# main.net
KiCad netlist of a schematic drawn in EAGLE
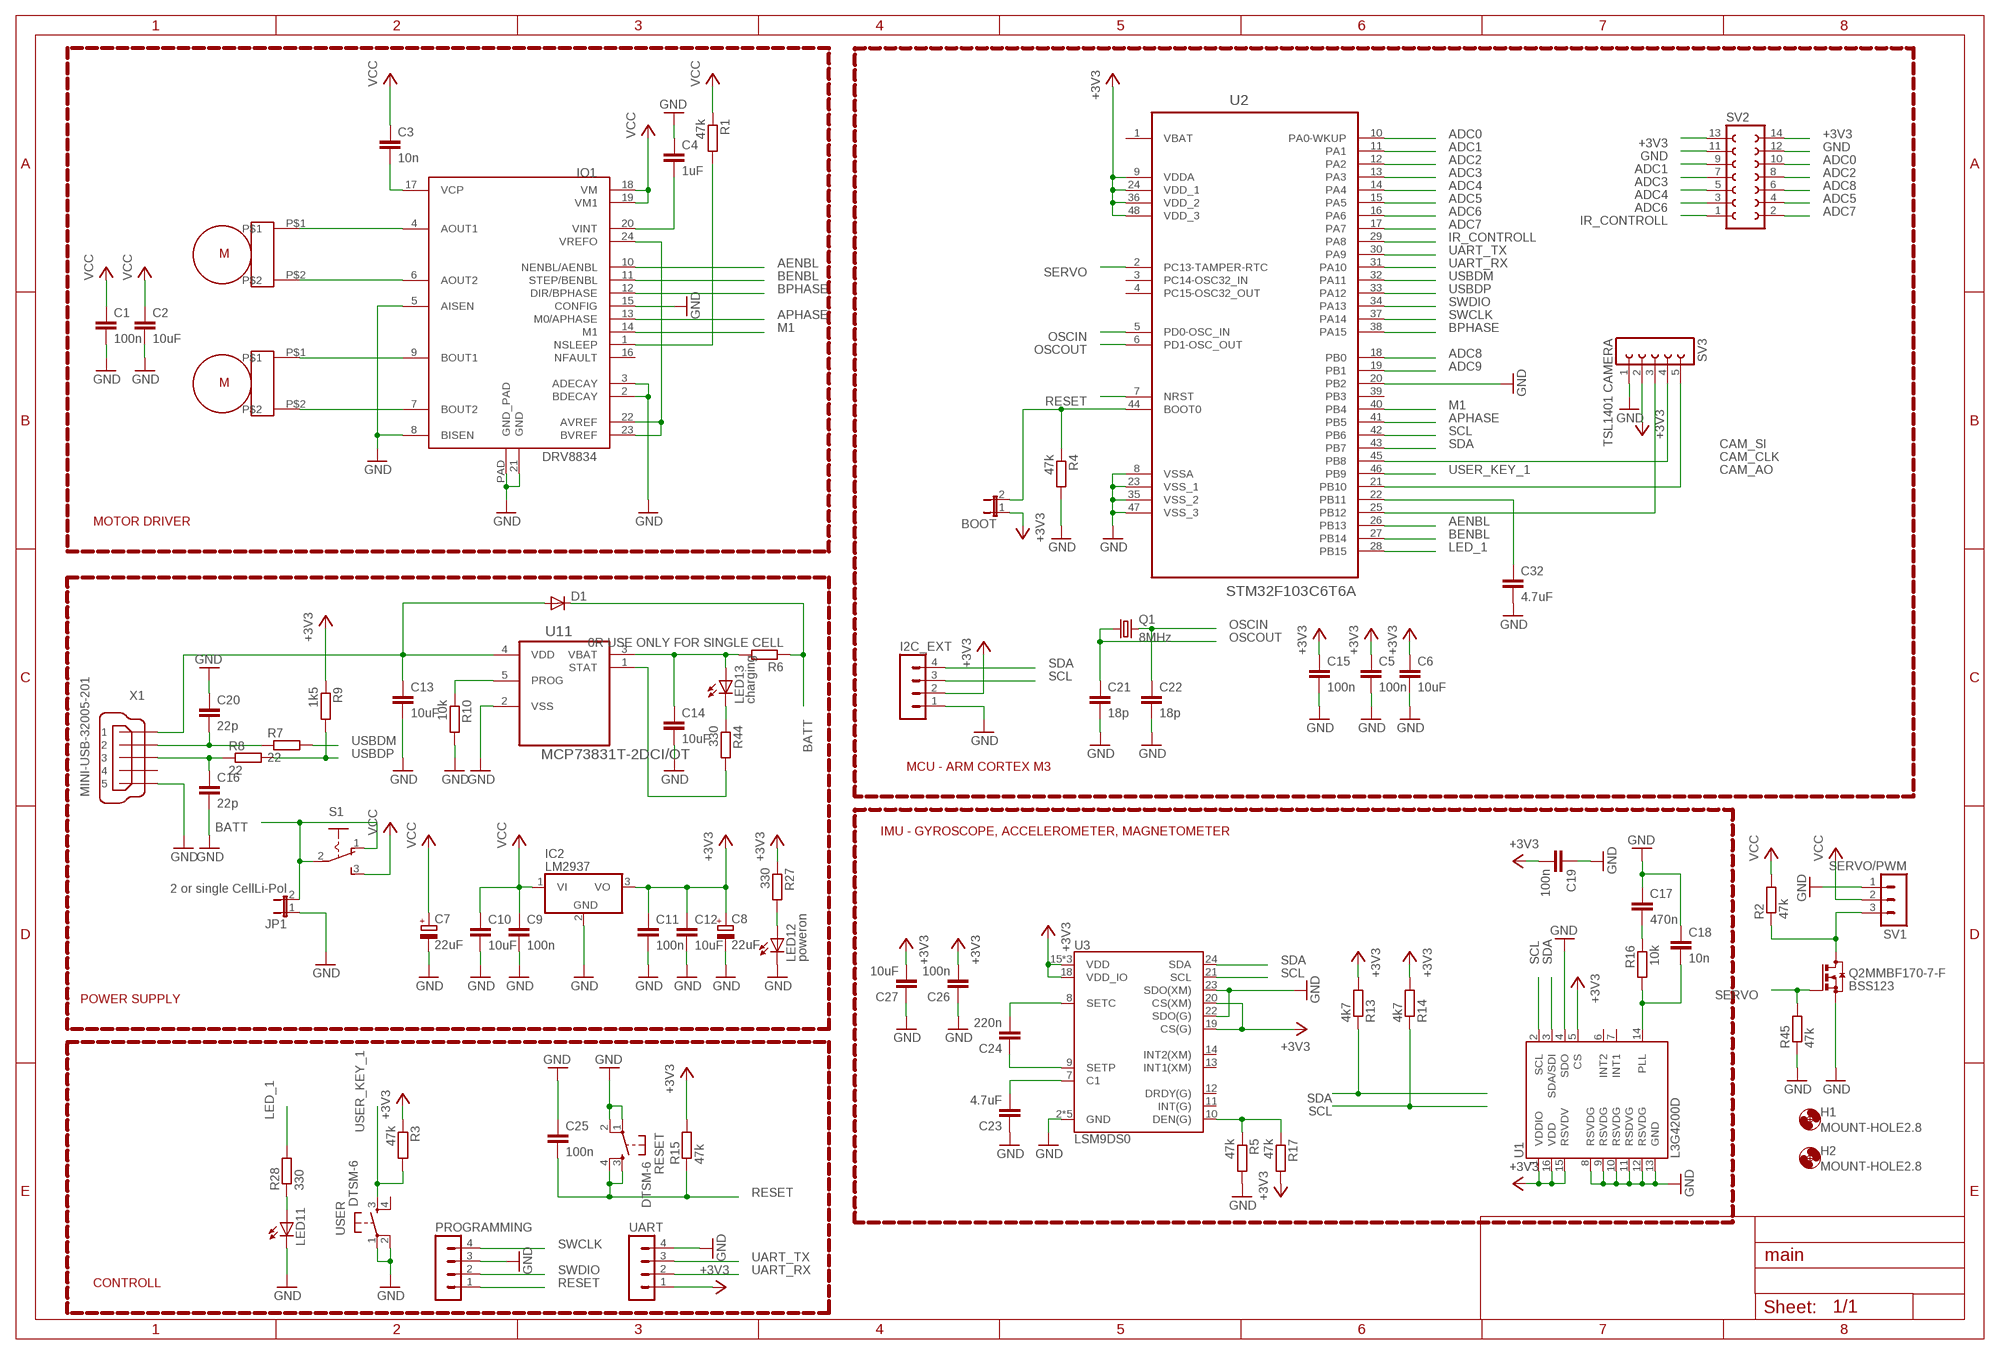
[diagram p0: schematic, sheet 1, part 1 of 2]
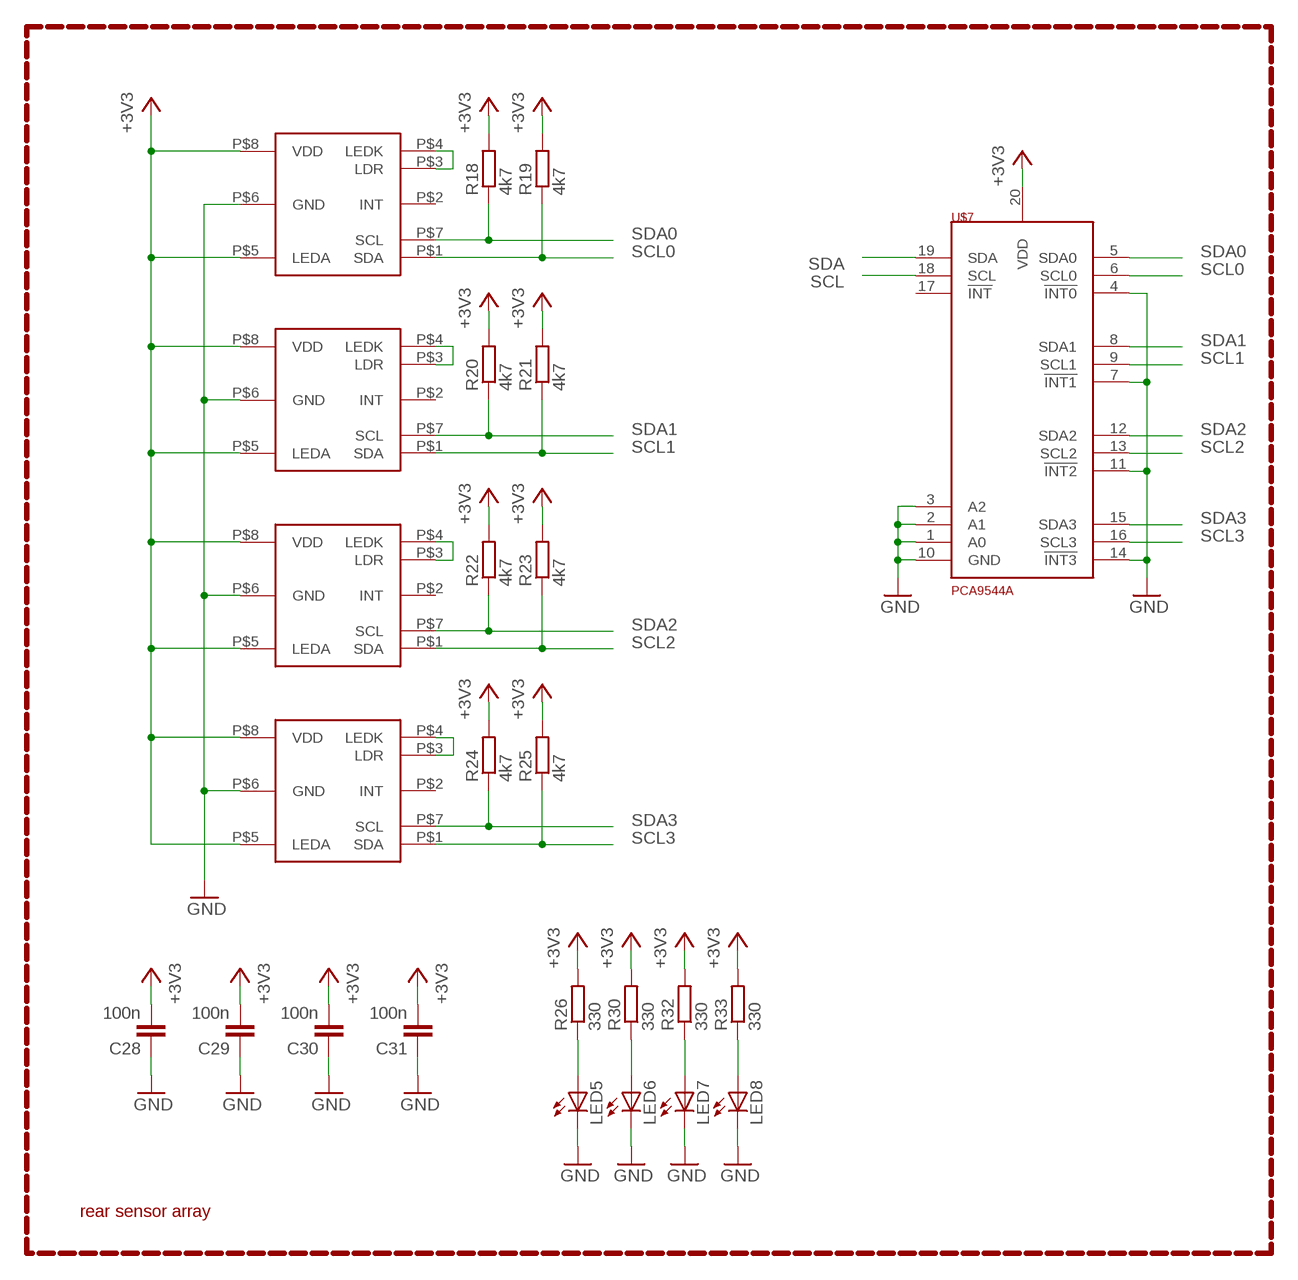
[diagram p1: schematic, sheet 1, part 2 of 2]

(export (version "E")
  (design (tool "Eeschema 10.0.6"))
  (components
    (comp (ref "BOOT")
      (value "JP1E")
      (footprint "eagle-import:JP1")
      (libsource (lib "eagle-import") (part "JP1E"))
    )
    (comp (ref "C1")
      (value "100n")
      (footprint "eagle-import:C1206")
      (libsource (lib "eagle-import") (part "C-EUC1206"))
    )
    (comp (ref "C2")
      (value "10uF")
      (footprint "eagle-import:C1206")
      (libsource (lib "eagle-import") (part "C-EUC1206"))
    )
    (comp (ref "C3")
      (value "10n")
      (footprint "eagle-import:C1206")
      (libsource (lib "eagle-import") (part "C-EUC1206"))
    )
    (comp (ref "C4")
      (value "1uF")
      (footprint "eagle-import:C1206")
      (libsource (lib "eagle-import") (part "C-EUC1206"))
    )
    (comp (ref "C5")
      (value "100n")
      (footprint "eagle-import:C0805")
      (libsource (lib "eagle-import") (part "C-EUC0805"))
    )
    (comp (ref "C6")
      (value "10uF")
      (footprint "eagle-import:C0805")
      (libsource (lib "eagle-import") (part "C-EUC0805"))
    )
    (comp (ref "C7")
      (value "22uF")
      (footprint "eagle-import:153CLV-0505")
      (libsource (lib "eagle-import") (part "CPOL-EU153CLV-0505"))
    )
    (comp (ref "C8")
      (value "22uF")
      (footprint "eagle-import:153CLV-0505")
      (libsource (lib "eagle-import") (part "CPOL-EU153CLV-0505"))
    )
    (comp (ref "C9")
      (value "100n")
      (footprint "eagle-import:C0805")
      (libsource (lib "eagle-import") (part "C-EUC0805"))
    )
    (comp (ref "C10")
      (value "10uF")
      (footprint "eagle-import:C0805")
      (libsource (lib "eagle-import") (part "C-EUC0805"))
    )
    (comp (ref "C11")
      (value "100n")
      (footprint "eagle-import:C0805")
      (libsource (lib "eagle-import") (part "C-EUC0805"))
    )
    (comp (ref "C12")
      (value "10uF")
      (footprint "eagle-import:C0805")
      (libsource (lib "eagle-import") (part "C-EUC0805"))
    )
    (comp (ref "C13")
      (value "10uF")
      (footprint "eagle-import:C0805")
      (libsource (lib "eagle-import") (part "C-EUC0805"))
    )
    (comp (ref "C14")
      (value "10uF")
      (footprint "eagle-import:C0805")
      (libsource (lib "eagle-import") (part "C-EUC0805"))
    )
    (comp (ref "C15")
      (value "100n")
      (footprint "eagle-import:C0805")
      (libsource (lib "eagle-import") (part "C-EUC0805"))
    )
    (comp (ref "C16")
      (value "22p")
      (footprint "eagle-import:C0805")
      (libsource (lib "eagle-import") (part "C-EUC0805"))
    )
    (comp (ref "C17")
      (value "470n")
      (footprint "eagle-import:C0805")
      (libsource (lib "eagle-import") (part "C-EUC0805"))
    )
    (comp (ref "C18")
      (value "10n")
      (footprint "eagle-import:C0805")
      (libsource (lib "eagle-import") (part "C-EUC0805"))
    )
    (comp (ref "C19")
      (value "100n")
      (footprint "eagle-import:C0805")
      (libsource (lib "eagle-import") (part "C-EUC0805"))
    )
    (comp (ref "C20")
      (value "22p")
      (footprint "eagle-import:C0805")
      (libsource (lib "eagle-import") (part "C-EUC0805"))
    )
    (comp (ref "C21")
      (value "18p")
      (footprint "eagle-import:C0805")
      (libsource (lib "eagle-import") (part "C-EUC0805"))
    )
    (comp (ref "C22")
      (value "18p")
      (footprint "eagle-import:C0805")
      (libsource (lib "eagle-import") (part "C-EUC0805"))
    )
    (comp (ref "C23")
      (value "4.7uF")
      (footprint "eagle-import:C0805")
      (libsource (lib "eagle-import") (part "C-EUC0805"))
    )
    (comp (ref "C24")
      (value "220n")
      (footprint "eagle-import:C0805")
      (libsource (lib "eagle-import") (part "C-EUC0805"))
    )
    (comp (ref "C25")
      (value "100n")
      (footprint "eagle-import:C0805")
      (libsource (lib "eagle-import") (part "C-EUC0805"))
    )
    (comp (ref "C26")
      (value "100n")
      (footprint "eagle-import:C0805")
      (libsource (lib "eagle-import") (part "C-EUC0805"))
    )
    (comp (ref "C27")
      (value "10uF")
      (footprint "eagle-import:C0805")
      (libsource (lib "eagle-import") (part "C-EUC0805"))
    )
    (comp (ref "C28")
      (value "100n")
      (footprint "eagle-import:C0805")
      (libsource (lib "eagle-import") (part "C-EUC0805"))
    )
    (comp (ref "C29")
      (value "100n")
      (footprint "eagle-import:C0805")
      (libsource (lib "eagle-import") (part "C-EUC0805"))
    )
    (comp (ref "C30")
      (value "100n")
      (footprint "eagle-import:C0805")
      (libsource (lib "eagle-import") (part "C-EUC0805"))
    )
    (comp (ref "C31")
      (value "100n")
      (footprint "eagle-import:C0805")
      (libsource (lib "eagle-import") (part "C-EUC0805"))
    )
    (comp (ref "C32")
      (value "4.7uF")
      (footprint "eagle-import:C0805")
      (libsource (lib "eagle-import") (part "C-EUC0805"))
    )
    (comp (ref "D1")
      (value "DIODE-SMB")
      (footprint "eagle-import:SMB")
      (libsource (lib "eagle-import") (part "DIODE-SMB"))
    )
    (comp (ref "H1")
      (value "MOUNT-HOLE2.8")
      (footprint "eagle-import:2,8")
      (libsource (lib "eagle-import") (part "MOUNT-HOLE2.8"))
    )
    (comp (ref "H2")
      (value "MOUNT-HOLE2.8")
      (footprint "eagle-import:2,8")
      (libsource (lib "eagle-import") (part "MOUNT-HOLE2.8"))
    )
    (comp (ref "I2C_EXT")
      (value "MA04-1")
      (footprint "eagle-import:MA04-1")
      (libsource (lib "eagle-import") (part "MA04-1"))
    )
    (comp (ref "IC2")
      (value "LM2937")
      (footprint "eagle-import:TO263-3")
      (libsource (lib "eagle-import") (part "LM2937"))
    )
    (comp (ref "IO1")
      (value "DRV8834")
      (footprint "eagle-import:DRV8834_PCK")
      (libsource (lib "eagle-import") (part "DRV8834"))
    )
    (comp (ref "JP1")
      (value "2 or single CellLi-Pol")
      (footprint "eagle-import:JP1")
      (libsource (lib "eagle-import") (part "JP1E"))
    )
    (comp (ref "LED5")
      (value "LEDCHIPLED_1206")
      (footprint "eagle-import:CHIPLED_1206")
      (libsource (lib "eagle-import") (part "LEDCHIPLED_1206"))
    )
    (comp (ref "LED6")
      (value "LEDCHIPLED_1206")
      (footprint "eagle-import:CHIPLED_1206")
      (libsource (lib "eagle-import") (part "LEDCHIPLED_1206"))
    )
    (comp (ref "LED7")
      (value "LEDCHIPLED_1206")
      (footprint "eagle-import:CHIPLED_1206")
      (libsource (lib "eagle-import") (part "LEDCHIPLED_1206"))
    )
    (comp (ref "LED8")
      (value "LEDCHIPLED_1206")
      (footprint "eagle-import:CHIPLED_1206")
      (libsource (lib "eagle-import") (part "LEDCHIPLED_1206"))
    )
    (comp (ref "LED11")
      (value "LEDCHIPLED_1206")
      (footprint "eagle-import:CHIPLED_1206")
      (libsource (lib "eagle-import") (part "LEDCHIPLED_1206"))
    )
    (comp (ref "LED12")
      (value "poweron")
      (footprint "eagle-import:CHIPLED_1206")
      (libsource (lib "eagle-import") (part "LEDCHIPLED_1206"))
    )
    (comp (ref "LED13")
      (value "charging")
      (footprint "eagle-import:CHIPLED_1206")
      (libsource (lib "eagle-import") (part "LEDCHIPLED_1206"))
    )
    (comp (ref "PROGRAMMING")
      (value "MA04-1")
      (footprint "eagle-import:MA04-1")
      (libsource (lib "eagle-import") (part "MA04-1"))
    )
    (comp (ref "Q1")
      (value "8MHz")
      (footprint "eagle-import:CTS406")
      (libsource (lib "eagle-import") (part "CRYSTALCTS406"))
    )
    (comp (ref "Q2MMBF170-7-F")
      (value "BSS123")
      (footprint "eagle-import:SOT23")
      (libsource (lib "eagle-import") (part "BSS123"))
    )
    (comp (ref "R1")
      (value "47k")
      (footprint "eagle-import:M1206")
      (libsource (lib "eagle-import") (part "R-EU_M1206"))
    )
    (comp (ref "R2")
      (value "47k")
      (footprint "eagle-import:M0805")
      (libsource (lib "eagle-import") (part "R-EU_M0805"))
    )
    (comp (ref "R3")
      (value "47k")
      (footprint "eagle-import:M0805")
      (libsource (lib "eagle-import") (part "R-EU_M0805"))
    )
    (comp (ref "R4")
      (value "47k")
      (footprint "eagle-import:M0805")
      (libsource (lib "eagle-import") (part "R-EU_M0805"))
    )
    (comp (ref "R5")
      (value "47k")
      (footprint "eagle-import:M0805")
      (libsource (lib "eagle-import") (part "R-EU_M0805"))
    )
    (comp (ref "R6")
      (value "0R USE ONLY FOR SINGLE CELL")
      (footprint "eagle-import:M1206")
      (libsource (lib "eagle-import") (part "R-EU_M1206"))
    )
    (comp (ref "R7")
      (value "22")
      (footprint "eagle-import:M0805")
      (libsource (lib "eagle-import") (part "R-EU_M0805"))
    )
    (comp (ref "R8")
      (value "22")
      (footprint "eagle-import:M0805")
      (libsource (lib "eagle-import") (part "R-EU_M0805"))
    )
    (comp (ref "R9")
      (value "1k5")
      (footprint "eagle-import:M0805")
      (libsource (lib "eagle-import") (part "R-EU_M0805"))
    )
    (comp (ref "R10")
      (value "10k")
      (footprint "eagle-import:M0805")
      (libsource (lib "eagle-import") (part "R-EU_M0805"))
    )
    (comp (ref "R13")
      (value "4k7")
      (footprint "eagle-import:M0805")
      (libsource (lib "eagle-import") (part "R-EU_M0805"))
    )
    (comp (ref "R14")
      (value "4k7")
      (footprint "eagle-import:M0805")
      (libsource (lib "eagle-import") (part "R-EU_M0805"))
    )
    (comp (ref "R15")
      (value "47k")
      (footprint "eagle-import:M0805")
      (libsource (lib "eagle-import") (part "R-EU_M0805"))
    )
    (comp (ref "R16")
      (value "10k")
      (footprint "eagle-import:M0805")
      (libsource (lib "eagle-import") (part "R-EU_M0805"))
    )
    (comp (ref "R17")
      (value "47k")
      (footprint "eagle-import:M0805")
      (libsource (lib "eagle-import") (part "R-EU_M0805"))
    )
    (comp (ref "R18")
      (value "4k7")
      (footprint "eagle-import:M0805")
      (libsource (lib "eagle-import") (part "R-EU_M0805"))
    )
    (comp (ref "R19")
      (value "4k7")
      (footprint "eagle-import:M0805")
      (libsource (lib "eagle-import") (part "R-EU_M0805"))
    )
    (comp (ref "R20")
      (value "4k7")
      (footprint "eagle-import:M0805")
      (libsource (lib "eagle-import") (part "R-EU_M0805"))
    )
    (comp (ref "R21")
      (value "4k7")
      (footprint "eagle-import:M0805")
      (libsource (lib "eagle-import") (part "R-EU_M0805"))
    )
    (comp (ref "R22")
      (value "4k7")
      (footprint "eagle-import:M0805")
      (libsource (lib "eagle-import") (part "R-EU_M0805"))
    )
    (comp (ref "R23")
      (value "4k7")
      (footprint "eagle-import:M0805")
      (libsource (lib "eagle-import") (part "R-EU_M0805"))
    )
    (comp (ref "R24")
      (value "4k7")
      (footprint "eagle-import:M0805")
      (libsource (lib "eagle-import") (part "R-EU_M0805"))
    )
    (comp (ref "R25")
      (value "4k7")
      (footprint "eagle-import:M0805")
      (libsource (lib "eagle-import") (part "R-EU_M0805"))
    )
    (comp (ref "R26")
      (value "330")
      (footprint "eagle-import:M0805")
      (libsource (lib "eagle-import") (part "R-EU_M0805"))
    )
    (comp (ref "R27")
      (value "330")
      (footprint "eagle-import:M0805")
      (libsource (lib "eagle-import") (part "R-EU_M0805"))
    )
    (comp (ref "R28")
      (value "330")
      (footprint "eagle-import:M0805")
      (libsource (lib "eagle-import") (part "R-EU_M0805"))
    )
    (comp (ref "R30")
      (value "330")
      (footprint "eagle-import:M0805")
      (libsource (lib "eagle-import") (part "R-EU_M0805"))
    )
    (comp (ref "R32")
      (value "330")
      (footprint "eagle-import:M0805")
      (libsource (lib "eagle-import") (part "R-EU_M0805"))
    )
    (comp (ref "R33")
      (value "330")
      (footprint "eagle-import:M0805")
      (libsource (lib "eagle-import") (part "R-EU_M0805"))
    )
    (comp (ref "R44")
      (value "330")
      (footprint "eagle-import:M0805")
      (libsource (lib "eagle-import") (part "R-EU_M0805"))
    )
    (comp (ref "R45")
      (value "47k")
      (footprint "eagle-import:M0805")
      (libsource (lib "eagle-import") (part "R-EU_M0805"))
    )
    (comp (ref "RESET")
      (value "DTSM-6")
      (footprint "eagle-import:DTSM-6")
      (libsource (lib "eagle-import") (part "DTSM-6"))
    )
    (comp (ref "S1")
      (value "255SB")
      (footprint "eagle-import:255SB")
      (libsource (lib "eagle-import") (part "255SB"))
    )
    (comp (ref "SV1")
      (value "SERVO/PWM")
      (footprint "eagle-import:MA03-1")
      (libsource (lib "eagle-import") (part "MA03-1"))
    )
    (comp (ref "SV2")
      (value "FE07-2")
      (footprint "eagle-import:FE07-2")
      (libsource (lib "eagle-import") (part "FE07-2"))
    )
    (comp (ref "SV3")
      (value "TSL1401 CAMERA")
      (footprint "eagle-import:FE05-1")
      (libsource (lib "eagle-import") (part "FE05-1"))
    )
    (comp (ref "U$1")
      (value "MICRO_METAL_GEAR_MOTOR")
      (footprint "eagle-import:MICRO_METAL_GEAR_MOTOR")
      (libsource (lib "eagle-import") (part "MICRO_METAL_GEAR_MOTOR"))
    )
    (comp (ref "U$2")
      (value "MICRO_METAL_GEAR_MOTOR")
      (footprint "eagle-import:MICRO_METAL_GEAR_MOTOR")
      (libsource (lib "eagle-import") (part "MICRO_METAL_GEAR_MOTOR"))
    )
    (comp (ref "U$3")
      (value "APDS9950")
      (footprint "eagle-import:APDS9950")
      (libsource (lib "eagle-import") (part "APDS9950"))
    )
    (comp (ref "U$4")
      (value "APDS9950")
      (footprint "eagle-import:APDS9950")
      (libsource (lib "eagle-import") (part "APDS9950"))
    )
    (comp (ref "U$5")
      (value "APDS9950")
      (footprint "eagle-import:APDS9950")
      (libsource (lib "eagle-import") (part "APDS9950"))
    )
    (comp (ref "U$6")
      (value "APDS9950")
      (footprint "eagle-import:APDS9950")
      (libsource (lib "eagle-import") (part "APDS9950"))
    )
    (comp (ref "U$7")
      (value "DSSCIRCUITS_PCA9544A")
      (footprint "eagle-import:DSSCIRCUITS_TSSOP20")
      (libsource (lib "eagle-import") (part "DSSCIRCUITS_PCA9544A"))
    )
    (comp (ref "U1")
      (value "L3G4200D")
      (footprint "eagle-import:LGA16-4X4")
      (libsource (lib "eagle-import") (part "L3G4200D"))
    )
    (comp (ref "U2")
      (value "STM32F103C6T6A")
      (footprint "eagle-import:QFP50P900X900X160-48N")
      (libsource (lib "eagle-import") (part "STM32F103C6T6A"))
    )
    (comp (ref "U3")
      (value "LSM9DS0")
      (footprint "eagle-import:LGA-24")
      (libsource (lib "eagle-import") (part "LSM9DS0"))
    )
    (comp (ref "U11")
      (value "MCP73831T-2DCI/OT")
      (footprint "eagle-import:SOT95P270X145-5N")
      (libsource (lib "eagle-import") (part "MCP73831T-2DCI/OT"))
    )
    (comp (ref "UART")
      (value "MA04-1")
      (footprint "eagle-import:MA04-1")
      (libsource (lib "eagle-import") (part "MA04-1"))
    )
    (comp (ref "USER")
      (value "DTSM-6")
      (footprint "eagle-import:DTSM-6")
      (libsource (lib "eagle-import") (part "DTSM-6"))
    )
    (comp (ref "X1")
      (value "MINI-USB-32005-201")
      (footprint "eagle-import:32005-201")
      (libsource (lib "eagle-import") (part "MINI-USB-32005-201"))
    )
  )
  (nets
    (net (code "1") (name "+3V3") (class "Default")
      (node (ref "BOOT") (pin "1") (pinfunction "1_1") (pintype "passive"))
      (node (ref "C11") (pin "1") (pinfunction "1_1") (pintype "passive"))
      (node (ref "C12") (pin "1") (pinfunction "1_1") (pintype "passive"))
      (node (ref "C15") (pin "1") (pinfunction "1_1") (pintype "passive"))
      (node (ref "C19") (pin "2") (pinfunction "2_2") (pintype "passive"))
      (node (ref "C26") (pin "2") (pinfunction "2_2") (pintype "passive"))
      (node (ref "C27") (pin "2") (pinfunction "2_2") (pintype "passive"))
      (node (ref "C28") (pin "2") (pinfunction "2_2") (pintype "passive"))
      (node (ref "C29") (pin "2") (pinfunction "2_2") (pintype "passive"))
      (node (ref "C30") (pin "2") (pinfunction "2_2") (pintype "passive"))
      (node (ref "C31") (pin "2") (pinfunction "2_2") (pintype "passive"))
      (node (ref "C5") (pin "1") (pinfunction "1_1") (pintype "passive"))
      (node (ref "C6") (pin "1") (pinfunction "1_1") (pintype "passive"))
      (node (ref "C8") (pin "+") (pinfunction "+_+") (pintype "passive"))
      (node (ref "I2C_EXT") (pin "2") (pinfunction "2_2") (pintype "passive"))
      (node (ref "IC2") (pin "3") (pinfunction "VO_3") (pintype "passive"))
      (node (ref "R13") (pin "2") (pinfunction "2_2") (pintype "passive"))
      (node (ref "R14") (pin "2") (pinfunction "2_2") (pintype "passive"))
      (node (ref "R15") (pin "2") (pinfunction "2_2") (pintype "passive"))
      (node (ref "R17") (pin "2") (pinfunction "2_2") (pintype "passive"))
      (node (ref "R18") (pin "2") (pinfunction "2_2") (pintype "passive"))
      (node (ref "R19") (pin "2") (pinfunction "2_2") (pintype "passive"))
      (node (ref "R20") (pin "2") (pinfunction "2_2") (pintype "passive"))
      (node (ref "R21") (pin "2") (pinfunction "2_2") (pintype "passive"))
      (node (ref "R22") (pin "2") (pinfunction "2_2") (pintype "passive"))
      (node (ref "R23") (pin "2") (pinfunction "2_2") (pintype "passive"))
      (node (ref "R24") (pin "2") (pinfunction "2_2") (pintype "passive"))
      (node (ref "R25") (pin "2") (pinfunction "2_2") (pintype "passive"))
      (node (ref "R26") (pin "2") (pinfunction "2_2") (pintype "passive"))
      (node (ref "R27") (pin "1") (pinfunction "1_1") (pintype "passive"))
      (node (ref "R3") (pin "1") (pinfunction "1_1") (pintype "passive"))
      (node (ref "R30") (pin "2") (pinfunction "2_2") (pintype "passive"))
      (node (ref "R32") (pin "2") (pinfunction "2_2") (pintype "passive"))
      (node (ref "R33") (pin "2") (pinfunction "2_2") (pintype "passive"))
      (node (ref "R9") (pin "1") (pinfunction "1_1") (pintype "passive"))
      (node (ref "SV2") (pin "13") (pinfunction "13_13") (pintype "passive"))
      (node (ref "SV2") (pin "14") (pinfunction "14_14") (pintype "passive"))
      (node (ref "SV3") (pin "2") (pinfunction "2_2") (pintype "passive"))
      (node (ref "U$3") (pin "P$5") (pinfunction "LEDA_P$5") (pintype "bidirectional"))
      (node (ref "U$3") (pin "P$8") (pinfunction "VDD_P$8") (pintype "bidirectional"))
      (node (ref "U$4") (pin "P$5") (pinfunction "LEDA_P$5") (pintype "bidirectional"))
      (node (ref "U$4") (pin "P$8") (pinfunction "VDD_P$8") (pintype "bidirectional"))
      (node (ref "U$5") (pin "P$5") (pinfunction "LEDA_P$5") (pintype "bidirectional"))
      (node (ref "U$5") (pin "P$8") (pinfunction "VDD_P$8") (pintype "bidirectional"))
      (node (ref "U$6") (pin "P$5") (pinfunction "LEDA_P$5") (pintype "bidirectional"))
      (node (ref "U$6") (pin "P$8") (pinfunction "VDD_P$8") (pintype "bidirectional"))
      (node (ref "U$7") (pin "20") (pinfunction "VDD_20") (pintype "power_in"))
      (node (ref "U1") (pin "1") (pinfunction "VDDIO_1") (pintype "bidirectional"))
      (node (ref "U1") (pin "15") (pinfunction "RSVDV_15") (pintype "bidirectional"))
      (node (ref "U1") (pin "16") (pinfunction "VDD_16") (pintype "bidirectional"))
      (node (ref "U1") (pin "5") (pinfunction "CS_5") (pintype "bidirectional"))
      (node (ref "U2") (pin "24") (pinfunction "VDD_1_24") (pintype "power_in"))
      (node (ref "U2") (pin "36") (pinfunction "VDD_2_36") (pintype "power_in"))
      (node (ref "U2") (pin "48") (pinfunction "VDD_3_48") (pintype "power_in"))
      (node (ref "U2") (pin "9") (pinfunction "VDDA_9") (pintype "power_in"))
      (node (ref "U3") (pin "15") (pinfunction "VDD_15") (pintype "bidirectional"))
      (node (ref "U3") (pin "16") (pinfunction "VDD_16") (pintype "bidirectional"))
      (node (ref "U3") (pin "17") (pinfunction "VDD_17") (pintype "bidirectional"))
      (node (ref "U3") (pin "18") (pinfunction "VDD_IO_18") (pintype "bidirectional"))
      (node (ref "U3") (pin "19") (pinfunction "CS(G)_19") (pintype "bidirectional"))
      (node (ref "U3") (pin "20") (pinfunction "CS(XM)_20") (pintype "bidirectional"))
      (node (ref "UART") (pin "1") (pinfunction "1_1") (pintype "passive"))
    )
    (net (code "2") (name "/ADC0") (class "Default")
      (node (ref "SV2") (pin "10") (pinfunction "10_10") (pintype "passive"))
      (node (ref "U2") (pin "10") (pinfunction "PA0-WKUP_10") (pintype "bidirectional"))
    )
    (net (code "3") (name "/ADC1") (class "Default")
      (node (ref "SV2") (pin "9") (pinfunction "9_9") (pintype "passive"))
      (node (ref "U2") (pin "11") (pinfunction "PA1_11") (pintype "bidirectional"))
    )
    (net (code "4") (name "/ADC2") (class "Default")
      (node (ref "SV2") (pin "8") (pinfunction "8_8") (pintype "passive"))
      (node (ref "U2") (pin "12") (pinfunction "PA2_12") (pintype "bidirectional"))
    )
    (net (code "5") (name "/ADC3") (class "Default")
      (node (ref "SV2") (pin "7") (pinfunction "7_7") (pintype "passive"))
      (node (ref "U2") (pin "13") (pinfunction "PA3_13") (pintype "bidirectional"))
    )
    (net (code "6") (name "/ADC4") (class "Default")
      (node (ref "SV2") (pin "5") (pinfunction "5_5") (pintype "passive"))
      (node (ref "U2") (pin "14") (pinfunction "PA4_14") (pintype "bidirectional"))
    )
    (net (code "7") (name "/ADC5") (class "Default")
      (node (ref "SV2") (pin "4") (pinfunction "4_4") (pintype "passive"))
      (node (ref "U2") (pin "15") (pinfunction "PA5_15") (pintype "bidirectional"))
    )
    (net (code "8") (name "/ADC6") (class "Default")
      (node (ref "SV2") (pin "3") (pinfunction "3_3") (pintype "passive"))
      (node (ref "U2") (pin "16") (pinfunction "PA6_16") (pintype "bidirectional"))
    )
    (net (code "9") (name "/ADC7") (class "Default")
      (node (ref "SV2") (pin "2") (pinfunction "2_2") (pintype "passive"))
      (node (ref "U2") (pin "17") (pinfunction "PA7_17") (pintype "bidirectional"))
    )
    (net (code "10") (name "/ADC8") (class "Default")
      (node (ref "SV2") (pin "6") (pinfunction "6_6") (pintype "passive"))
      (node (ref "U2") (pin "18") (pinfunction "PB0_18") (pintype "bidirectional"))
    )
    (net (code "11") (name "/ADC9") (class "Default")
      (node (ref "U2") (pin "19") (pinfunction "PB1_19") (pintype "bidirectional"))
    )
    (net (code "12") (name "/AENBL") (class "Default")
      (node (ref "IO1") (pin "10") (pinfunction "NENBL/AENBL_10") (pintype "bidirectional"))
      (node (ref "U2") (pin "26") (pinfunction "PB13_26") (pintype "bidirectional"))
    )
    (net (code "13") (name "/APHASE") (class "Default")
      (node (ref "IO1") (pin "13") (pinfunction "M0/APHASE_13") (pintype "bidirectional"))
      (node (ref "U2") (pin "41") (pinfunction "PB5_41") (pintype "bidirectional"))
    )
    (net (code "14") (name "/BATT") (class "Default")
      (node (ref "D1") (pin "C") (pinfunction "C_C") (pintype "passive"))
      (node (ref "JP1") (pin "2") (pinfunction "2_2") (pintype "passive"))
      (node (ref "R6") (pin "1") (pinfunction "1_1") (pintype "passive"))
      (node (ref "S1") (pin "1") (pinfunction "O_1") (pintype "passive"))
      (node (ref "S1") (pin "2") (pinfunction "P_2") (pintype "passive"))
    )
    (net (code "15") (name "/BENBL") (class "Default")
      (node (ref "IO1") (pin "11") (pinfunction "STEP/BENBL_11") (pintype "bidirectional"))
      (node (ref "U2") (pin "27") (pinfunction "PB14_27") (pintype "bidirectional"))
    )
    (net (code "16") (name "/BPHASE") (class "Default")
      (node (ref "IO1") (pin "12") (pinfunction "DIR/BPHASE_12") (pintype "bidirectional"))
      (node (ref "U2") (pin "38") (pinfunction "PA15_38") (pintype "bidirectional"))
    )
    (net (code "17") (name "/CAM_AO") (class "Default")
      (node (ref "SV3") (pin "3") (pinfunction "3_3") (pintype "passive"))
      (node (ref "U2") (pin "25") (pinfunction "PB12_25") (pintype "bidirectional"))
    )
    (net (code "18") (name "/CAM_CLK") (class "Default")
      (node (ref "SV3") (pin "4") (pinfunction "4_4") (pintype "passive"))
      (node (ref "U2") (pin "45") (pinfunction "PB8_45") (pintype "bidirectional"))
    )
    (net (code "19") (name "/CAM_SI") (class "Default")
      (node (ref "SV3") (pin "5") (pinfunction "5_5") (pintype "passive"))
      (node (ref "U2") (pin "21") (pinfunction "PB10_21") (pintype "bidirectional"))
    )
    (net (code "20") (name "/IR_CONTROLL") (class "Default")
      (node (ref "SV2") (pin "1") (pinfunction "1_1") (pintype "passive"))
      (node (ref "U2") (pin "29") (pinfunction "PA8_29") (pintype "bidirectional"))
    )
    (net (code "21") (name "/LED_1") (class "Default")
      (node (ref "R28") (pin "2") (pinfunction "2_2") (pintype "passive"))
      (node (ref "U2") (pin "28") (pinfunction "PB15_28") (pintype "bidirectional"))
    )
    (net (code "22") (name "/M1") (class "Default")
      (node (ref "IO1") (pin "14") (pinfunction "M1_14") (pintype "bidirectional"))
      (node (ref "U2") (pin "40") (pinfunction "PB4_40") (pintype "bidirectional"))
    )
    (net (code "23") (name "/OSCIN") (class "Default")
      (node (ref "C22") (pin "1") (pinfunction "1_1") (pintype "passive"))
      (node (ref "Q1") (pin "3") (pinfunction "2_3") (pintype "passive"))
      (node (ref "U2") (pin "5") (pinfunction "PD0-OSC_IN_5") (pintype "bidirectional"))
    )
    (net (code "24") (name "/OSCOUT") (class "Default")
      (node (ref "C21") (pin "1") (pinfunction "1_1") (pintype "passive"))
      (node (ref "Q1") (pin "1") (pinfunction "1_1") (pintype "passive"))
      (node (ref "U2") (pin "6") (pinfunction "PD1-OSC_OUT_6") (pintype "bidirectional"))
    )
    (net (code "25") (name "/RESET") (class "Default")
      (node (ref "C25") (pin "2") (pinfunction "2_2") (pintype "passive"))
      (node (ref "PROGRAMMING") (pin "1") (pinfunction "1_1") (pintype "passive"))
      (node (ref "R15") (pin "1") (pinfunction "1_1") (pintype "passive"))
      (node (ref "RESET") (pin "3") (pinfunction "3_3") (pintype "passive"))
      (node (ref "RESET") (pin "4") (pinfunction "4_4") (pintype "passive"))
      (node (ref "U2") (pin "7") (pinfunction "NRST_7") (pintype "bidirectional"))
    )
    (net (code "26") (name "/SCL") (class "Default")
      (node (ref "I2C_EXT") (pin "3") (pinfunction "3_3") (pintype "passive"))
      (node (ref "R14") (pin "1") (pinfunction "1_1") (pintype "passive"))
      (node (ref "U$7") (pin "18") (pinfunction "SCL_18") (pintype "bidirectional"))
      (node (ref "U1") (pin "2") (pinfunction "SCL_2") (pintype "bidirectional"))
      (node (ref "U2") (pin "42") (pinfunction "PB6_42") (pintype "bidirectional"))
      (node (ref "U3") (pin "21") (pinfunction "SCL_21") (pintype "bidirectional"))
    )
    (net (code "27") (name "/SCL0") (class "Default")
      (node (ref "R19") (pin "1") (pinfunction "1_1") (pintype "passive"))
      (node (ref "U$3") (pin "P$1") (pinfunction "SDA_P$1") (pintype "bidirectional"))
      (node (ref "U$7") (pin "6") (pinfunction "SCL0_6") (pintype "bidirectional"))
    )
    (net (code "28") (name "/SCL1") (class "Default")
      (node (ref "R21") (pin "1") (pinfunction "1_1") (pintype "passive"))
      (node (ref "U$4") (pin "P$1") (pinfunction "SDA_P$1") (pintype "bidirectional"))
      (node (ref "U$7") (pin "9") (pinfunction "SCL1_9") (pintype "bidirectional"))
    )
    (net (code "29") (name "/SCL2") (class "Default")
      (node (ref "R23") (pin "1") (pinfunction "1_1") (pintype "passive"))
      (node (ref "U$5") (pin "P$1") (pinfunction "SDA_P$1") (pintype "bidirectional"))
      (node (ref "U$7") (pin "13") (pinfunction "SCL2_13") (pintype "bidirectional"))
    )
    (net (code "30") (name "/SCL3") (class "Default")
      (node (ref "R25") (pin "1") (pinfunction "1_1") (pintype "passive"))
      (node (ref "U$6") (pin "P$1") (pinfunction "SDA_P$1") (pintype "bidirectional"))
      (node (ref "U$7") (pin "16") (pinfunction "SCL3_16") (pintype "bidirectional"))
    )
    (net (code "31") (name "/SDA") (class "Default")
      (node (ref "I2C_EXT") (pin "4") (pinfunction "4_4") (pintype "passive"))
      (node (ref "R13") (pin "1") (pinfunction "1_1") (pintype "passive"))
      (node (ref "U$7") (pin "19") (pinfunction "SDA_19") (pintype "bidirectional"))
      (node (ref "U1") (pin "3") (pinfunction "SDA/SDI_3") (pintype "bidirectional"))
      (node (ref "U2") (pin "43") (pinfunction "PB7_43") (pintype "bidirectional"))
      (node (ref "U3") (pin "24") (pinfunction "SDA_24") (pintype "bidirectional"))
    )
    (net (code "32") (name "/SDA0") (class "Default")
      (node (ref "R18") (pin "1") (pinfunction "1_1") (pintype "passive"))
      (node (ref "U$3") (pin "P$7") (pinfunction "SCL_P$7") (pintype "bidirectional"))
      (node (ref "U$7") (pin "5") (pinfunction "SDA0_5") (pintype "bidirectional"))
    )
    (net (code "33") (name "/SDA1") (class "Default")
      (node (ref "R20") (pin "1") (pinfunction "1_1") (pintype "passive"))
      (node (ref "U$4") (pin "P$7") (pinfunction "SCL_P$7") (pintype "bidirectional"))
      (node (ref "U$7") (pin "8") (pinfunction "SDA1_8") (pintype "bidirectional"))
    )
    (net (code "34") (name "/SDA2") (class "Default")
      (node (ref "R22") (pin "1") (pinfunction "1_1") (pintype "passive"))
      (node (ref "U$5") (pin "P$7") (pinfunction "SCL_P$7") (pintype "bidirectional"))
      (node (ref "U$7") (pin "12") (pinfunction "SDA2_12") (pintype "bidirectional"))
    )
    (net (code "35") (name "/SDA3") (class "Default")
      (node (ref "R24") (pin "1") (pinfunction "1_1") (pintype "passive"))
      (node (ref "U$6") (pin "P$7") (pinfunction "SCL_P$7") (pintype "bidirectional"))
      (node (ref "U$7") (pin "15") (pinfunction "SDA3_15") (pintype "bidirectional"))
    )
    (net (code "36") (name "/SERVO") (class "Default")
      (node (ref "Q2MMBF170-7-F") (pin "1") (pinfunction "G_1") (pintype "passive"))
      (node (ref "R45") (pin "2") (pinfunction "2_2") (pintype "passive"))
      (node (ref "U2") (pin "2") (pinfunction "PC13-TAMPER-RTC_2") (pintype "bidirectional"))
    )
    (net (code "37") (name "/SWCLK") (class "Default")
      (node (ref "PROGRAMMING") (pin "4") (pinfunction "4_4") (pintype "passive"))
      (node (ref "U2") (pin "37") (pinfunction "PA14_37") (pintype "bidirectional"))
    )
    (net (code "38") (name "/SWDIO") (class "Default")
      (node (ref "PROGRAMMING") (pin "2") (pinfunction "2_2") (pintype "passive"))
      (node (ref "U2") (pin "34") (pinfunction "PA13_34") (pintype "bidirectional"))
    )
    (net (code "39") (name "/UART_RX") (class "Default")
      (node (ref "U2") (pin "31") (pinfunction "PA10_31") (pintype "bidirectional"))
      (node (ref "UART") (pin "2") (pinfunction "2_2") (pintype "passive"))
    )
    (net (code "40") (name "/UART_TX") (class "Default")
      (node (ref "U2") (pin "30") (pinfunction "PA9_30") (pintype "bidirectional"))
      (node (ref "UART") (pin "3") (pinfunction "3_3") (pintype "passive"))
    )
    (net (code "41") (name "/USBDM") (class "Default")
      (node (ref "R7") (pin "2") (pinfunction "2_2") (pintype "passive"))
      (node (ref "U2") (pin "32") (pinfunction "PA11_32") (pintype "bidirectional"))
    )
    (net (code "42") (name "/USBDP") (class "Default")
      (node (ref "R8") (pin "2") (pinfunction "2_2") (pintype "passive"))
      (node (ref "R9") (pin "2") (pinfunction "2_2") (pintype "passive"))
      (node (ref "U2") (pin "33") (pinfunction "PA12_33") (pintype "bidirectional"))
    )
    (net (code "43") (name "/USER_KEY_1") (class "Default")
      (node (ref "R3") (pin "2") (pinfunction "2_2") (pintype "passive"))
      (node (ref "U2") (pin "46") (pinfunction "PB9_46") (pintype "bidirectional"))
      (node (ref "USER") (pin "3") (pinfunction "3_3") (pintype "passive"))
    )
    (net (code "44") (name "/VBAT") (class "Default")
      (node (ref "U2") (pin "1") (pinfunction "VBAT_1") (pintype "power_in"))
    )
    (net (code "45") (name "GND") (class "Default")
      (node (ref "C1") (pin "2") (pinfunction "2_2") (pintype "passive"))
      (node (ref "C10") (pin "2") (pinfunction "2_2") (pintype "passive"))
      (node (ref "C11") (pin "2") (pinfunction "2_2") (pintype "passive"))
      (node (ref "C12") (pin "2") (pinfunction "2_2") (pintype "passive"))
      (node (ref "C13") (pin "2") (pinfunction "2_2") (pintype "passive"))
      (node (ref "C14") (pin "2") (pinfunction "2_2") (pintype "passive"))
      (node (ref "C15") (pin "2") (pinfunction "2_2") (pintype "passive"))
      (node (ref "C16") (pin "2") (pinfunction "2_2") (pintype "passive"))
      (node (ref "C17") (pin "1") (pinfunction "1_1") (pintype "passive"))
      (node (ref "C18") (pin "1") (pinfunction "1_1") (pintype "passive"))
      (node (ref "C19") (pin "1") (pinfunction "1_1") (pintype "passive"))
      (node (ref "C2") (pin "2") (pinfunction "2_2") (pintype "passive"))
      (node (ref "C20") (pin "1") (pinfunction "1_1") (pintype "passive"))
      (node (ref "C21") (pin "2") (pinfunction "2_2") (pintype "passive"))
      (node (ref "C22") (pin "2") (pinfunction "2_2") (pintype "passive"))
      (node (ref "C23") (pin "1") (pinfunction "1_1") (pintype "passive"))
      (node (ref "C25") (pin "1") (pinfunction "1_1") (pintype "passive"))
      (node (ref "C26") (pin "1") (pinfunction "1_1") (pintype "passive"))
      (node (ref "C27") (pin "1") (pinfunction "1_1") (pintype "passive"))
      (node (ref "C28") (pin "1") (pinfunction "1_1") (pintype "passive"))
      (node (ref "C29") (pin "1") (pinfunction "1_1") (pintype "passive"))
      (node (ref "C30") (pin "1") (pinfunction "1_1") (pintype "passive"))
      (node (ref "C31") (pin "1") (pinfunction "1_1") (pintype "passive"))
      (node (ref "C32") (pin "2") (pinfunction "2_2") (pintype "passive"))
      (node (ref "C4") (pin "1") (pinfunction "1_1") (pintype "passive"))
      (node (ref "C5") (pin "2") (pinfunction "2_2") (pintype "passive"))
      (node (ref "C6") (pin "2") (pinfunction "2_2") (pintype "passive"))
      (node (ref "C7") (pin "-") (pinfunction "-_-") (pintype "passive"))
      (node (ref "C8") (pin "-") (pinfunction "-_-") (pintype "passive"))
      (node (ref "C9") (pin "2") (pinfunction "2_2") (pintype "passive"))
      (node (ref "I2C_EXT") (pin "1") (pinfunction "1_1") (pintype "passive"))
      (node (ref "IC2") (pin "2") (pinfunction "GND_2") (pintype "passive"))
      (node (ref "IO1") (pin "15") (pinfunction "CONFIG_15") (pintype "bidirectional"))
      (node (ref "IO1") (pin "2") (pinfunction "BDECAY_2") (pintype "bidirectional"))
      (node (ref "IO1") (pin "21") (pinfunction "GND_21") (pintype "bidirectional"))
      (node (ref "IO1") (pin "3") (pinfunction "ADECAY_3") (pintype "bidirectional"))
      (node (ref "IO1") (pin "5") (pinfunction "AISEN_5") (pintype "bidirectional"))
      (node (ref "IO1") (pin "8") (pinfunction "BISEN_8") (pintype "bidirectional"))
      (node (ref "IO1") (pin "PAD") (pinfunction "GND_PAD_PAD") (pintype "bidirectional"))
      (node (ref "JP1") (pin "1") (pinfunction "1_1") (pintype "passive"))
      (node (ref "LED11") (pin "C") (pinfunction "C_C") (pintype "passive"))
      (node (ref "LED12") (pin "C") (pinfunction "C_C") (pintype "passive"))
      (node (ref "LED5") (pin "C") (pinfunction "C_C") (pintype "passive"))
      (node (ref "LED6") (pin "C") (pinfunction "C_C") (pintype "passive"))
      (node (ref "LED7") (pin "C") (pinfunction "C_C") (pintype "passive"))
      (node (ref "LED8") (pin "C") (pinfunction "C_C") (pintype "passive"))
      (node (ref "PROGRAMMING") (pin "3") (pinfunction "3_3") (pintype "passive"))
      (node (ref "Q2MMBF170-7-F") (pin "2") (pinfunction "S_2") (pintype "passive"))
      (node (ref "R10") (pin "2") (pinfunction "2_2") (pintype "passive"))
      (node (ref "R4") (pin "2") (pinfunction "2_2") (pintype "passive"))
      (node (ref "R45") (pin "1") (pinfunction "1_1") (pintype "passive"))
      (node (ref "R5") (pin "2") (pinfunction "2_2") (pintype "passive"))
      (node (ref "RESET") (pin "1") (pinfunction "1_1") (pintype "passive"))
      (node (ref "RESET") (pin "2") (pinfunction "2_2") (pintype "passive"))
      (node (ref "SV1") (pin "1") (pinfunction "1_1") (pintype "passive"))
      (node (ref "SV2") (pin "11") (pinfunction "11_11") (pintype "passive"))
      (node (ref "SV2") (pin "12") (pinfunction "12_12") (pintype "passive"))
      (node (ref "SV3") (pin "1") (pinfunction "1_1") (pintype "passive"))
      (node (ref "U$3") (pin "P$6") (pinfunction "GND_P$6") (pintype "bidirectional"))
      (node (ref "U$4") (pin "P$6") (pinfunction "GND_P$6") (pintype "bidirectional"))
      (node (ref "U$5") (pin "P$6") (pinfunction "GND_P$6") (pintype "bidirectional"))
      (node (ref "U$6") (pin "P$6") (pinfunction "GND_P$6") (pintype "bidirectional"))
      (node (ref "U$7") (pin "1") (pinfunction "A0_1") (pintype "input"))
      (node (ref "U$7") (pin "10") (pinfunction "GND_10") (pintype "power_in"))
      (node (ref "U$7") (pin "11") (pinfunction "~{INT2}_11") (pintype "input"))
      (node (ref "U$7") (pin "14") (pinfunction "~{INT3}_14") (pintype "input"))
      (node (ref "U$7") (pin "2") (pinfunction "A1_2") (pintype "input"))
      (node (ref "U$7") (pin "3") (pinfunction "A2_3") (pintype "input"))
      (node (ref "U$7") (pin "4") (pinfunction "~{INT0}_4") (pintype "input"))
      (node (ref "U$7") (pin "7") (pinfunction "~{INT1}_7") (pintype "input"))
      (node (ref "U1") (pin "10") (pinfunction "RSVDG_10") (pintype "bidirectional"))
      (node (ref "U1") (pin "11") (pinfunction "RSDVG_11") (pintype "bidirectional"))
      (node (ref "U1") (pin "12") (pinfunction "RSVDG_12") (pintype "bidirectional"))
      (node (ref "U1") (pin "13") (pinfunction "GND_13") (pintype "bidirectional"))
      (node (ref "U1") (pin "4") (pinfunction "SDO_4") (pintype "bidirectional"))
      (node (ref "U1") (pin "8") (pinfunction "RSVDG_8") (pintype "bidirectional"))
      (node (ref "U1") (pin "9") (pinfunction "RSVDG_9") (pintype "bidirectional"))
      (node (ref "U11") (pin "2") (pinfunction "VSS_2") (pintype "power_in"))
      (node (ref "U2") (pin "20") (pinfunction "PB2_20") (pintype "bidirectional"))
      (node (ref "U2") (pin "23") (pinfunction "VSS_1_23") (pintype "passive"))
      (node (ref "U2") (pin "35") (pinfunction "VSS_2_35") (pintype "passive"))
      (node (ref "U2") (pin "47") (pinfunction "VSS_3_47") (pintype "passive"))
      (node (ref "U2") (pin "8") (pinfunction "VSSA_8") (pintype "passive"))
      (node (ref "U3") (pin "2") (pinfunction "GND_2") (pintype "bidirectional"))
      (node (ref "U3") (pin "22") (pinfunction "SDO(G)_22") (pintype "bidirectional"))
      (node (ref "U3") (pin "23") (pinfunction "SDO(XM)_23") (pintype "bidirectional"))
      (node (ref "U3") (pin "3") (pinfunction "GND_3") (pintype "bidirectional"))
      (node (ref "U3") (pin "4") (pinfunction "GND_4") (pintype "bidirectional"))
      (node (ref "U3") (pin "5") (pinfunction "GND_5") (pintype "bidirectional"))
      (node (ref "U3") (pin "6") (pinfunction "GND_6") (pintype "bidirectional"))
      (node (ref "UART") (pin "4") (pinfunction "4_4") (pintype "passive"))
      (node (ref "USER") (pin "1") (pinfunction "1_1") (pintype "passive"))
      (node (ref "USER") (pin "2") (pinfunction "2_2") (pintype "passive"))
      (node (ref "X1") (pin "5") (pinfunction "5_5") (pintype "passive"))
    )
    (net (code "46") (name "Net-(C16-Pad1)") (class "Default")
      (node (ref "C16") (pin "1") (pinfunction "1_1") (pintype "passive"))
      (node (ref "R8") (pin "1") (pinfunction "1_1") (pintype "passive"))
      (node (ref "X1") (pin "3") (pinfunction "3_3") (pintype "passive"))
    )
    (net (code "47") (name "Net-(C17-Pad2)") (class "Default")
      (node (ref "C17") (pin "2") (pinfunction "2_2") (pintype "passive"))
      (node (ref "R16") (pin "1") (pinfunction "1_1") (pintype "passive"))
    )
    (net (code "48") (name "Net-(C20-Pad2)") (class "Default")
      (node (ref "C20") (pin "2") (pinfunction "2_2") (pintype "passive"))
      (node (ref "R7") (pin "1") (pinfunction "1_1") (pintype "passive"))
      (node (ref "X1") (pin "2") (pinfunction "2_2") (pintype "passive"))
    )
    (net (code "49") (name "Net-(IO1-AOUT1)") (class "Default")
      (node (ref "IO1") (pin "4") (pinfunction "AOUT1_4") (pintype "bidirectional"))
      (node (ref "U$1") (pin "P$1") (pinfunction "P$1_P$1") (pintype "bidirectional"))
    )
    (net (code "50") (name "Net-(IO1-AOUT2)") (class "Default")
      (node (ref "IO1") (pin "6") (pinfunction "AOUT2_6") (pintype "bidirectional"))
      (node (ref "U$1") (pin "P$2") (pinfunction "P$2_P$2") (pintype "bidirectional"))
    )
    (net (code "51") (name "Net-(IO1-AVREF)") (class "Default")
      (node (ref "IO1") (pin "22") (pinfunction "AVREF_22") (pintype "bidirectional"))
      (node (ref "IO1") (pin "23") (pinfunction "BVREF_23") (pintype "bidirectional"))
      (node (ref "IO1") (pin "24") (pinfunction "VREFO_24") (pintype "bidirectional"))
    )
    (net (code "52") (name "Net-(IO1-BOUT1)") (class "Default")
      (node (ref "IO1") (pin "9") (pinfunction "BOUT1_9") (pintype "bidirectional"))
      (node (ref "U$2") (pin "P$1") (pinfunction "P$1_P$1") (pintype "bidirectional"))
    )
    (net (code "53") (name "Net-(IO1-BOUT2)") (class "Default")
      (node (ref "IO1") (pin "7") (pinfunction "BOUT2_7") (pintype "bidirectional"))
      (node (ref "U$2") (pin "P$2") (pinfunction "P$2_P$2") (pintype "bidirectional"))
    )
    (net (code "54") (name "Net-(IO1-NSLEEP)") (class "Default")
      (node (ref "IO1") (pin "1") (pinfunction "NSLEEP_1") (pintype "bidirectional"))
      (node (ref "R1") (pin "2") (pinfunction "2_2") (pintype "passive"))
    )
    (net (code "55") (name "Net-(IO1-VCP)") (class "Default")
      (node (ref "C3") (pin "2") (pinfunction "2_2") (pintype "passive"))
      (node (ref "IO1") (pin "17") (pinfunction "VCP_17") (pintype "bidirectional"))
    )
    (net (code "56") (name "Net-(IO1-VINT)") (class "Default")
      (node (ref "C4") (pin "2") (pinfunction "2_2") (pintype "passive"))
      (node (ref "IO1") (pin "20") (pinfunction "VINT_20") (pintype "bidirectional"))
    )
    (net (code "57") (name "Net-(LED5-PadA)") (class "Default")
      (node (ref "LED5") (pin "A") (pinfunction "A_A") (pintype "passive"))
      (node (ref "R26") (pin "1") (pinfunction "1_1") (pintype "passive"))
    )
    (net (code "58") (name "Net-(LED6-PadA)") (class "Default")
      (node (ref "LED6") (pin "A") (pinfunction "A_A") (pintype "passive"))
      (node (ref "R30") (pin "1") (pinfunction "1_1") (pintype "passive"))
    )
    (net (code "59") (name "Net-(LED7-PadA)") (class "Default")
      (node (ref "LED7") (pin "A") (pinfunction "A_A") (pintype "passive"))
      (node (ref "R32") (pin "1") (pinfunction "1_1") (pintype "passive"))
    )
    (net (code "60") (name "Net-(LED8-PadA)") (class "Default")
      (node (ref "LED8") (pin "A") (pinfunction "A_A") (pintype "passive"))
      (node (ref "R33") (pin "1") (pinfunction "1_1") (pintype "passive"))
    )
    (net (code "61") (name "Net-(LED11-PadA)") (class "Default")
      (node (ref "LED11") (pin "A") (pinfunction "A_A") (pintype "passive"))
      (node (ref "R28") (pin "1") (pinfunction "1_1") (pintype "passive"))
    )
    (net (code "62") (name "Net-(LED12-PadA)") (class "Default")
      (node (ref "LED12") (pin "A") (pinfunction "A_A") (pintype "passive"))
      (node (ref "R27") (pin "2") (pinfunction "2_2") (pintype "passive"))
    )
    (net (code "63") (name "Net-(LED13-PadC)") (class "Default")
      (node (ref "LED13") (pin "C") (pinfunction "C_C") (pintype "passive"))
      (node (ref "R44") (pin "1") (pinfunction "1_1") (pintype "passive"))
    )
    (net (code "64") (name "Net-(Q2MMBF170-7-F-D)") (class "Default")
      (node (ref "Q2MMBF170-7-F") (pin "3") (pinfunction "D_3") (pintype "passive"))
      (node (ref "R2") (pin "1") (pinfunction "1_1") (pintype "passive"))
      (node (ref "SV1") (pin "3") (pinfunction "3_3") (pintype "passive"))
    )
    (net (code "65") (name "Net-(U$3-LDR)") (class "Default")
      (node (ref "U$3") (pin "P$3") (pinfunction "LDR_P$3") (pintype "bidirectional"))
      (node (ref "U$3") (pin "P$4") (pinfunction "LEDK_P$4") (pintype "bidirectional"))
    )
    (net (code "66") (name "Net-(U$4-LDR)") (class "Default")
      (node (ref "U$4") (pin "P$3") (pinfunction "LDR_P$3") (pintype "bidirectional"))
      (node (ref "U$4") (pin "P$4") (pinfunction "LEDK_P$4") (pintype "bidirectional"))
    )
    (net (code "67") (name "Net-(U$5-LDR)") (class "Default")
      (node (ref "U$5") (pin "P$3") (pinfunction "LDR_P$3") (pintype "bidirectional"))
      (node (ref "U$5") (pin "P$4") (pinfunction "LEDK_P$4") (pintype "bidirectional"))
    )
    (net (code "68") (name "Net-(U$6-LDR)") (class "Default")
      (node (ref "U$6") (pin "P$3") (pinfunction "LDR_P$3") (pintype "bidirectional"))
      (node (ref "U$6") (pin "P$4") (pinfunction "LEDK_P$4") (pintype "bidirectional"))
    )
    (net (code "69") (name "Net-(U1-PLL)") (class "Default")
      (node (ref "C18") (pin "2") (pinfunction "2_2") (pintype "passive"))
      (node (ref "R16") (pin "2") (pinfunction "2_2") (pintype "passive"))
      (node (ref "U1") (pin "14") (pinfunction "PLL_14") (pintype "bidirectional"))
    )
    (net (code "70") (name "Net-(U2-BOOT0)") (class "Default")
      (node (ref "BOOT") (pin "2") (pinfunction "2_2") (pintype "passive"))
      (node (ref "R4") (pin "1") (pinfunction "1_1") (pintype "passive"))
      (node (ref "U2") (pin "44") (pinfunction "BOOT0_44") (pintype "input"))
    )
    (net (code "71") (name "Net-(U2-PB11)") (class "Default")
      (node (ref "C32") (pin "1") (pinfunction "1_1") (pintype "passive"))
      (node (ref "U2") (pin "22") (pinfunction "PB11_22") (pintype "bidirectional"))
    )
    (net (code "72") (name "Net-(U3-C1)") (class "Default")
      (node (ref "C23") (pin "2") (pinfunction "2_2") (pintype "passive"))
      (node (ref "U3") (pin "7") (pinfunction "C1_7") (pintype "bidirectional"))
    )
    (net (code "73") (name "Net-(U3-DEN(G))") (class "Default")
      (node (ref "R17") (pin "1") (pinfunction "1_1") (pintype "passive"))
      (node (ref "R5") (pin "1") (pinfunction "1_1") (pintype "passive"))
      (node (ref "U3") (pin "10") (pinfunction "DEN(G)_10") (pintype "bidirectional"))
    )
    (net (code "74") (name "Net-(U3-SETC)") (class "Default")
      (node (ref "C24") (pin "2") (pinfunction "2_2") (pintype "passive"))
      (node (ref "U3") (pin "8") (pinfunction "SETC_8") (pintype "bidirectional"))
    )
    (net (code "75") (name "Net-(U3-SETP)") (class "Default")
      (node (ref "C24") (pin "1") (pinfunction "1_1") (pintype "passive"))
      (node (ref "U3") (pin "9") (pinfunction "SETP_9") (pintype "bidirectional"))
    )
    (net (code "76") (name "Net-(U11-PROG)") (class "Default")
      (node (ref "R10") (pin "1") (pinfunction "1_1") (pintype "passive"))
      (node (ref "U11") (pin "5") (pinfunction "PROG_5") (pintype "input"))
    )
    (net (code "77") (name "Net-(U11-STAT)") (class "Default")
      (node (ref "R44") (pin "2") (pinfunction "2_2") (pintype "passive"))
      (node (ref "U11") (pin "1") (pinfunction "STAT_1") (pintype "output"))
    )
    (net (code "78") (name "Net-(U11-VBAT)") (class "Default")
      (node (ref "C14") (pin "1") (pinfunction "1_1") (pintype "passive"))
      (node (ref "LED13") (pin "A") (pinfunction "A_A") (pintype "passive"))
      (node (ref "R6") (pin "2") (pinfunction "2_2") (pintype "passive"))
      (node (ref "U11") (pin "3") (pinfunction "VBAT_3") (pintype "power_in"))
    )
    (net (code "79") (name "Net-(U11-VDD)") (class "Default")
      (node (ref "C13") (pin "1") (pinfunction "1_1") (pintype "passive"))
      (node (ref "D1") (pin "A") (pinfunction "A_A") (pintype "passive"))
      (node (ref "U11") (pin "4") (pinfunction "VDD_4") (pintype "power_in"))
      (node (ref "X1") (pin "1") (pinfunction "1_1") (pintype "passive"))
    )
    (net (code "80") (name "VCC") (class "Default")
      (node (ref "C1") (pin "1") (pinfunction "1_1") (pintype "passive"))
      (node (ref "C10") (pin "1") (pinfunction "1_1") (pintype "passive"))
      (node (ref "C2") (pin "1") (pinfunction "1_1") (pintype "passive"))
      (node (ref "C3") (pin "1") (pinfunction "1_1") (pintype "passive"))
      (node (ref "C7") (pin "+") (pinfunction "+_+") (pintype "passive"))
      (node (ref "C9") (pin "1") (pinfunction "1_1") (pintype "passive"))
      (node (ref "IC2") (pin "1") (pinfunction "VI_1") (pintype "input"))
      (node (ref "IO1") (pin "18") (pinfunction "VM_18") (pintype "bidirectional"))
      (node (ref "IO1") (pin "19") (pinfunction "VM1_19") (pintype "bidirectional"))
      (node (ref "R1") (pin "1") (pinfunction "1_1") (pintype "passive"))
      (node (ref "R2") (pin "2") (pinfunction "2_2") (pintype "passive"))
      (node (ref "S1") (pin "3") (pinfunction "S_3") (pintype "passive"))
      (node (ref "SV1") (pin "2") (pinfunction "2_2") (pintype "passive"))
    )
    (net (code "81") (name "unconnected-(IO1-NFAULT-Pad16)") (class "Default")
      (node (ref "IO1") (pin "16") (pinfunction "NFAULT_16") (pintype "bidirectional"))
    )
    (net (code "82") (name "unconnected-(U$3-INT-PadP$2)") (class "Default")
      (node (ref "U$3") (pin "P$2") (pinfunction "INT_P$2") (pintype "bidirectional"))
    )
    (net (code "83") (name "unconnected-(U$4-INT-PadP$2)") (class "Default")
      (node (ref "U$4") (pin "P$2") (pinfunction "INT_P$2") (pintype "bidirectional"))
    )
    (net (code "84") (name "unconnected-(U$5-INT-PadP$2)") (class "Default")
      (node (ref "U$5") (pin "P$2") (pinfunction "INT_P$2") (pintype "bidirectional"))
    )
    (net (code "85") (name "unconnected-(U$6-INT-PadP$2)") (class "Default")
      (node (ref "U$6") (pin "P$2") (pinfunction "INT_P$2") (pintype "bidirectional"))
    )
    (net (code "86") (name "unconnected-(U$7-~{INT}-Pad17)") (class "Default")
      (node (ref "U$7") (pin "17") (pinfunction "~{INT}_17") (pintype "output"))
    )
    (net (code "87") (name "unconnected-(U1-INT1-Pad7)") (class "Default")
      (node (ref "U1") (pin "7") (pinfunction "INT1_7") (pintype "bidirectional"))
    )
    (net (code "88") (name "unconnected-(U1-INT2-Pad6)") (class "Default")
      (node (ref "U1") (pin "6") (pinfunction "INT2_6") (pintype "bidirectional"))
    )
    (net (code "89") (name "unconnected-(U2-PB3-Pad39)") (class "Default")
      (node (ref "U2") (pin "39") (pinfunction "PB3_39") (pintype "bidirectional"))
    )
    (net (code "90") (name "unconnected-(U2-PC14-OSC32_IN-Pad3)") (class "Default")
      (node (ref "U2") (pin "3") (pinfunction "PC14-OSC32_IN_3") (pintype "bidirectional"))
    )
    (net (code "91") (name "unconnected-(U2-PC15-OSC32_OUT-Pad4)") (class "Default")
      (node (ref "U2") (pin "4") (pinfunction "PC15-OSC32_OUT_4") (pintype "bidirectional"))
    )
    (net (code "92") (name "unconnected-(U3-DRDY(G)-Pad12)") (class "Default")
      (node (ref "U3") (pin "12") (pinfunction "DRDY(G)_12") (pintype "bidirectional"))
    )
    (net (code "93") (name "unconnected-(U3-INT(G)-Pad11)") (class "Default")
      (node (ref "U3") (pin "11") (pinfunction "INT(G)_11") (pintype "bidirectional"))
    )
    (net (code "94") (name "unconnected-(U3-INT1(XM)-Pad13)") (class "Default")
      (node (ref "U3") (pin "13") (pinfunction "INT1(XM)_13") (pintype "bidirectional"))
    )
    (net (code "95") (name "unconnected-(U3-INT2(XM)-Pad14)") (class "Default")
      (node (ref "U3") (pin "14") (pinfunction "INT2(XM)_14") (pintype "bidirectional"))
    )
    (net (code "96") (name "unconnected-(USER-Pad4)") (class "Default")
      (node (ref "USER") (pin "4") (pinfunction "4_4") (pintype "passive"))
    )
    (net (code "97") (name "unconnected-(X1-Pad4)") (class "Default")
      (node (ref "X1") (pin "4") (pinfunction "4_4") (pintype "passive"))
    )
  )
)
